# easyface485.net
KiCad netlist of a schematic drawn in EAGLE
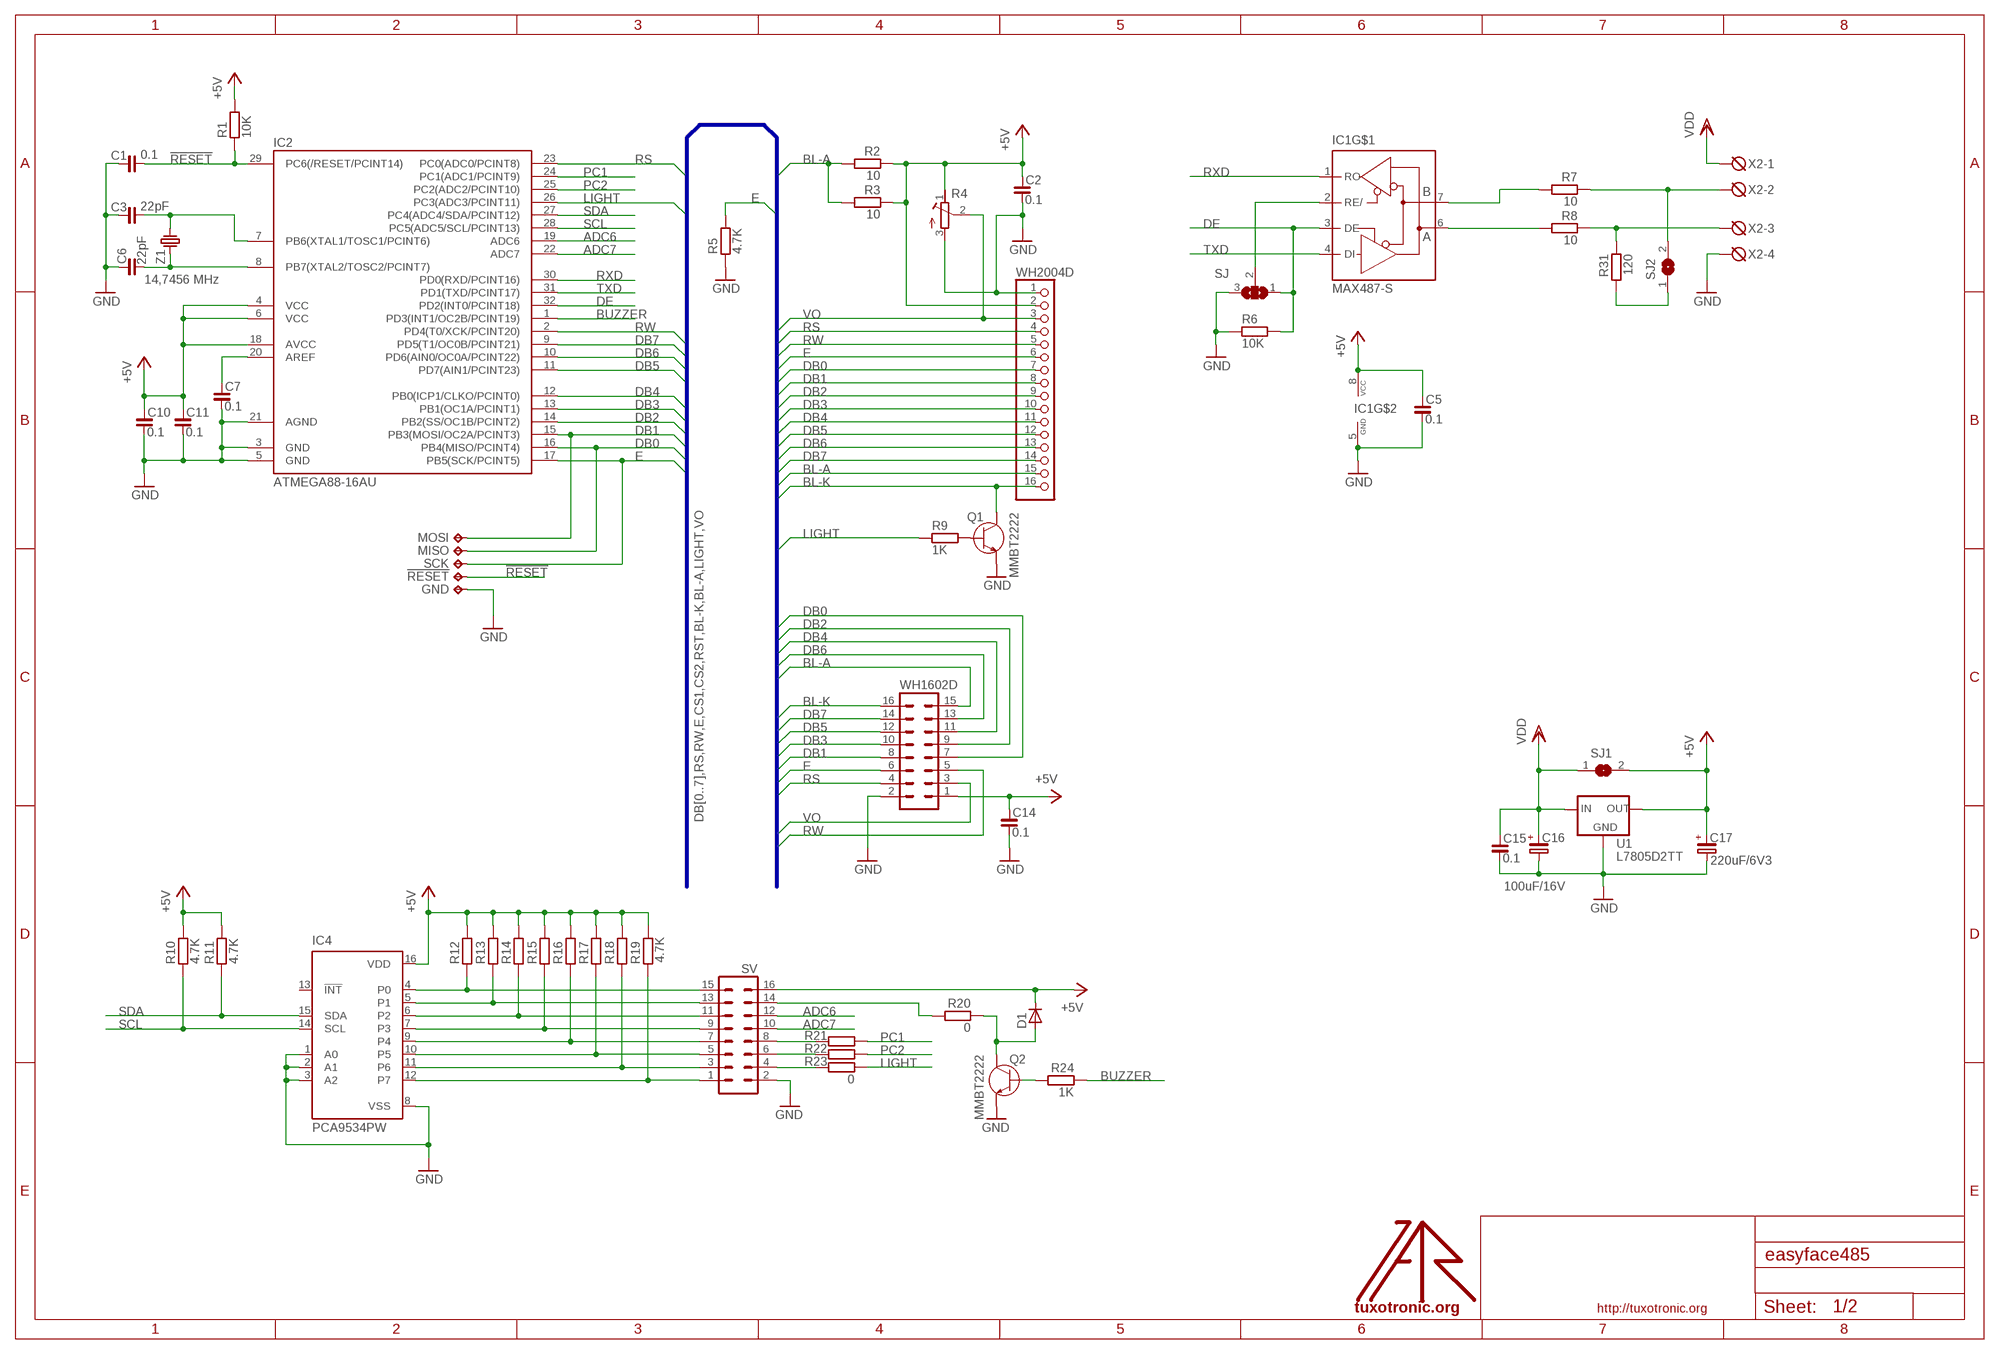
[diagram p0: schematic, sheet 1]
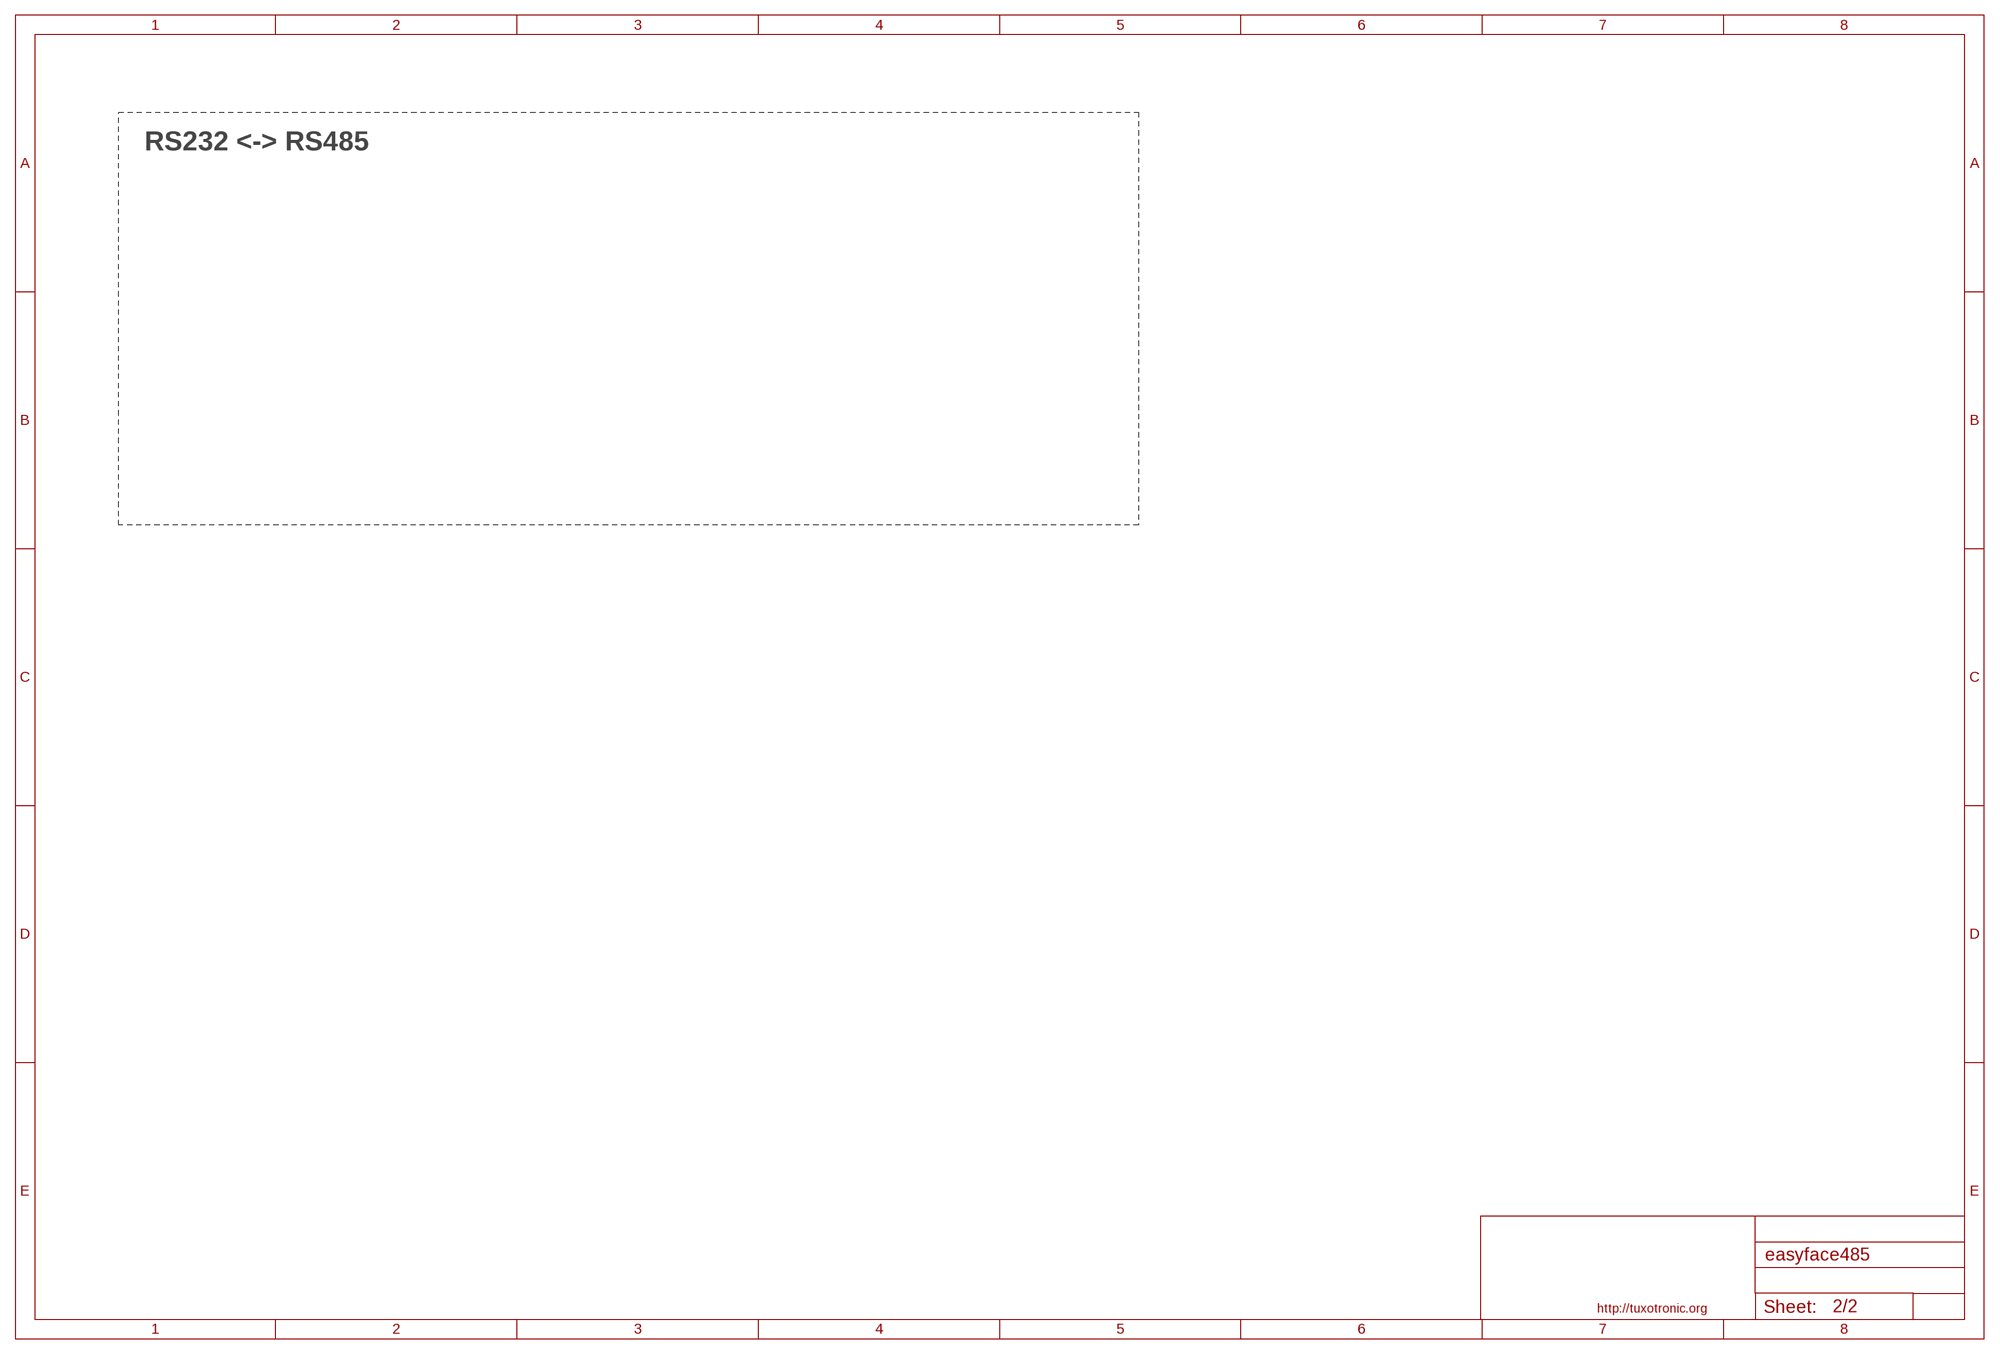
[diagram p1: schematic, sheet 2]

(export (version "E")
  (design (tool "Eeschema 10.0.6"))
  (components
    (comp (ref "!RESET")
      (value "TPB1,27")
      (footprint "eagle-import:B1,27")
      (libsource (lib "eagle-import") (part "TPB1,27"))
    )
    (comp (ref "C1")
      (value "0.1")
      (footprint "eagle-import:C0805")
      (libsource (lib "eagle-import") (part "C_0805"))
    )
    (comp (ref "C2")
      (value "0.1")
      (footprint "eagle-import:C0805")
      (libsource (lib "eagle-import") (part "C_0805"))
    )
    (comp (ref "C3")
      (value "22pF")
      (footprint "eagle-import:C0805")
      (libsource (lib "eagle-import") (part "C_0805"))
    )
    (comp (ref "C5")
      (value "0.1")
      (footprint "eagle-import:C0805")
      (libsource (lib "eagle-import") (part "C_0805"))
    )
    (comp (ref "C6")
      (value "22pF")
      (footprint "eagle-import:C0805")
      (libsource (lib "eagle-import") (part "C_0805"))
    )
    (comp (ref "C7")
      (value "0.1")
      (footprint "eagle-import:C0805")
      (libsource (lib "eagle-import") (part "C_0805"))
    )
    (comp (ref "C10")
      (value "0.1")
      (footprint "eagle-import:C0805")
      (libsource (lib "eagle-import") (part "C_0805"))
    )
    (comp (ref "C11")
      (value "0.1")
      (footprint "eagle-import:C0805")
      (libsource (lib "eagle-import") (part "C_0805"))
    )
    (comp (ref "C14")
      (value "0.1")
      (footprint "eagle-import:C0805")
      (libsource (lib "eagle-import") (part "C_0805"))
    )
    (comp (ref "C15")
      (value "0.1")
      (footprint "eagle-import:C0805")
      (libsource (lib "eagle-import") (part "C_0805"))
    )
    (comp (ref "C16")
      (value "100uF/16V")
      (footprint "eagle-import:SMC_D")
      (libsource (lib "eagle-import") (part "CP_SMCD"))
    )
    (comp (ref "C17")
      (value "220uF/6V3")
      (footprint "eagle-import:SMC_D")
      (libsource (lib "eagle-import") (part "CP_SMCD"))
    )
    (comp (ref "D1")
      (value "D-SOD-80")
      (footprint "eagle-import:SOD80")
      (libsource (lib "eagle-import") (part "D-SOD-80"))
    )
    (comp (ref "GND")
      (value "TPB1,27")
      (footprint "eagle-import:B1,27")
      (libsource (lib "eagle-import") (part "TPB1,27"))
    )
    (comp (ref "IC1")
      (value "MAX487-S")
      (footprint "eagle-import:SO08")
      (libsource (lib "eagle-import") (part "MAX487-S"))
    )
    (comp (ref "IC2")
      (value "ATMEGA88-16AU")
      (footprint "eagle-import:TQFP32-08")
      (libsource (lib "eagle-import") (part "MEGA48/88/168-AU"))
    )
    (comp (ref "IC4")
      (value "PCA9534PW")
      (footprint "eagle-import:SSOP16")
      (libsource (lib "eagle-import") (part "PCA9534PW"))
    )
    (comp (ref "MISO")
      (value "TPB1,27")
      (footprint "eagle-import:B1,27")
      (libsource (lib "eagle-import") (part "TPB1,27"))
    )
    (comp (ref "MOSI")
      (value "TPB1,27")
      (footprint "eagle-import:B1,27")
      (libsource (lib "eagle-import") (part "TPB1,27"))
    )
    (comp (ref "Q1")
      (value "MMBT2222")
      (footprint "eagle-import:SOT23")
      (libsource (lib "eagle-import") (part "BC847C"))
    )
    (comp (ref "Q2")
      (value "MMBT2222")
      (footprint "eagle-import:SOT23")
      (libsource (lib "eagle-import") (part "BC847C"))
    )
    (comp (ref "R1")
      (value "10K")
      (footprint "eagle-import:R0805")
      (libsource (lib "eagle-import") (part "R_0805"))
    )
    (comp (ref "R2")
      (value "10")
      (footprint "eagle-import:R0805")
      (libsource (lib "eagle-import") (part "R_0805"))
    )
    (comp (ref "R3")
      (value "10")
      (footprint "eagle-import:R0805")
      (libsource (lib "eagle-import") (part "R_0805"))
    )
    (comp (ref "R4")
      (value "RTRIM")
      (footprint "eagle-import:RTRIM-3362P")
      (libsource (lib "eagle-import") (part "RTRIM"))
    )
    (comp (ref "R5")
      (value "4.7K")
      (footprint "eagle-import:R0805")
      (libsource (lib "eagle-import") (part "R_0805"))
    )
    (comp (ref "R6")
      (value "10K")
      (footprint "eagle-import:R0805")
      (libsource (lib "eagle-import") (part "R_0805"))
    )
    (comp (ref "R7")
      (value "10")
      (footprint "eagle-import:R0805")
      (libsource (lib "eagle-import") (part "R_0805"))
    )
    (comp (ref "R8")
      (value "10")
      (footprint "eagle-import:R0805")
      (libsource (lib "eagle-import") (part "R_0805"))
    )
    (comp (ref "R9")
      (value "1K")
      (footprint "eagle-import:R0805")
      (libsource (lib "eagle-import") (part "R_0805"))
    )
    (comp (ref "R10")
      (value "4.7K")
      (footprint "eagle-import:R0805")
      (libsource (lib "eagle-import") (part "R_0805"))
    )
    (comp (ref "R11")
      (value "4.7K")
      (footprint "eagle-import:R0805")
      (libsource (lib "eagle-import") (part "R_0805"))
    )
    (comp (ref "R12")
      (value "4.7K")
      (footprint "eagle-import:R0805")
      (libsource (lib "eagle-import") (part "R_0805"))
    )
    (comp (ref "R13")
      (value "4.7K")
      (footprint "eagle-import:R0805")
      (libsource (lib "eagle-import") (part "R_0805"))
    )
    (comp (ref "R14")
      (value "4.7K")
      (footprint "eagle-import:R0805")
      (libsource (lib "eagle-import") (part "R_0805"))
    )
    (comp (ref "R15")
      (value "4.7K")
      (footprint "eagle-import:R0805")
      (libsource (lib "eagle-import") (part "R_0805"))
    )
    (comp (ref "R16")
      (value "4.7K")
      (footprint "eagle-import:R0805")
      (libsource (lib "eagle-import") (part "R_0805"))
    )
    (comp (ref "R17")
      (value "4.7K")
      (footprint "eagle-import:R0805")
      (libsource (lib "eagle-import") (part "R_0805"))
    )
    (comp (ref "R18")
      (value "4.7K")
      (footprint "eagle-import:R0805")
      (libsource (lib "eagle-import") (part "R_0805"))
    )
    (comp (ref "R19")
      (value "4.7K")
      (footprint "eagle-import:R0805")
      (libsource (lib "eagle-import") (part "R_0805"))
    )
    (comp (ref "R20")
      (value "0")
      (footprint "eagle-import:R0805")
      (libsource (lib "eagle-import") (part "R_0805"))
    )
    (comp (ref "R21")
      (value "0")
      (footprint "eagle-import:R0805")
      (libsource (lib "eagle-import") (part "R_0805"))
    )
    (comp (ref "R22")
      (value "0")
      (footprint "eagle-import:R0805")
      (libsource (lib "eagle-import") (part "R_0805"))
    )
    (comp (ref "R23")
      (value "0")
      (footprint "eagle-import:R0805")
      (libsource (lib "eagle-import") (part "R_0805"))
    )
    (comp (ref "R24")
      (value "1K")
      (footprint "eagle-import:R0805")
      (libsource (lib "eagle-import") (part "R_0805"))
    )
    (comp (ref "R31")
      (value "120")
      (footprint "eagle-import:R0805")
      (libsource (lib "eagle-import") (part "R_0805"))
    )
    (comp (ref "SCK")
      (value "TPB1,27")
      (footprint "eagle-import:B1,27")
      (libsource (lib "eagle-import") (part "TPB1,27"))
    )
    (comp (ref "SJ")
      (value "SJ2W")
      (footprint "eagle-import:SJ_2")
      (libsource (lib "eagle-import") (part "SJ2W"))
    )
    (comp (ref "SJ1") (value "SJ") (footprint "eagle-import:SJ") (libsource (lib "eagle-import") (part "SJ")))
    (comp (ref "SJ2") (value "SJ") (footprint "eagle-import:SJ") (libsource (lib "eagle-import") (part "SJ")))
    (comp (ref "SV")
      (value "ML16L")
      (footprint "eagle-import:ML16L")
      (libsource (lib "eagle-import") (part "ML16L"))
    )
    (comp (ref "U$")
      (value "LOGO")
      (footprint "eagle-import:TT_LOGO")
      (libsource (lib "eagle-import") (part "LOGO"))
    )
    (comp (ref "U1")
      (value "L7805D2TT")
      (footprint "eagle-import:D2PAK")
      (libsource (lib "eagle-import") (part "L78D2TT"))
    )
    (comp (ref "WH1602D")
      (value "MA08-2")
      (footprint "eagle-import:MA08-2")
      (libsource (lib "eagle-import") (part "MA08-2"))
    )
    (comp (ref "WH2004D")
      (value "PINHD-1X16_2.54-RND")
      (footprint "eagle-import:1X16RND")
      (libsource (lib "eagle-import") (part "PINHD-1X16_2.54-RND"))
    )
    (comp (ref "X2")
      (value "DG3XX-04-3.5")
      (footprint "eagle-import:DG350-3.5-04P")
      (libsource (lib "eagle-import") (part "DG3XX-04-3.5"))
    )
    (comp (ref "Z1")
      (value "14,7456 MHz")
      (footprint "eagle-import:HC49_S")
      (libsource (lib "eagle-import") (part "CRYSTAL-HC49S"))
    )
  )
  (nets
    (net (code "4") (name "+5V") (class "Default")
      (node (ref "C10") (pin "1") (pinfunction "1_1") (pintype "passive"))
      (node (ref "C11") (pin "1") (pinfunction "1_1") (pintype "passive"))
      (node (ref "C14") (pin "1") (pinfunction "1_1") (pintype "passive"))
      (node (ref "C17") (pin "+") (pinfunction "+_+") (pintype "passive"))
      (node (ref "C2") (pin "1") (pinfunction "1_1") (pintype "passive"))
      (node (ref "C5") (pin "1") (pinfunction "1_1") (pintype "passive"))
      (node (ref "D1") (pin "C") (pinfunction "C_C") (pintype "passive"))
      (node (ref "IC1") (pin "8") (pinfunction "VCC_8") (pintype "power_in"))
      (node (ref "IC2") (pin "18") (pinfunction "AVCC_18") (pintype "passive"))
      (node (ref "IC2") (pin "4") (pinfunction "VCC_4") (pintype "power_in"))
      (node (ref "IC2") (pin "6") (pinfunction "VCC_6") (pintype "power_in"))
      (node (ref "IC4") (pin "16") (pinfunction "VDD_16") (pintype "power_in"))
      (node (ref "R1") (pin "2") (pinfunction "2_2") (pintype "passive"))
      (node (ref "R10") (pin "2") (pinfunction "2_2") (pintype "passive"))
      (node (ref "R11") (pin "2") (pinfunction "2_2") (pintype "passive"))
      (node (ref "R12") (pin "2") (pinfunction "2_2") (pintype "passive"))
      (node (ref "R13") (pin "2") (pinfunction "2_2") (pintype "passive"))
      (node (ref "R14") (pin "2") (pinfunction "2_2") (pintype "passive"))
      (node (ref "R15") (pin "2") (pinfunction "2_2") (pintype "passive"))
      (node (ref "R16") (pin "2") (pinfunction "2_2") (pintype "passive"))
      (node (ref "R17") (pin "2") (pinfunction "2_2") (pintype "passive"))
      (node (ref "R18") (pin "2") (pinfunction "2_2") (pintype "passive"))
      (node (ref "R19") (pin "2") (pinfunction "2_2") (pintype "passive"))
      (node (ref "R2") (pin "1") (pinfunction "1_1") (pintype "passive"))
      (node (ref "R3") (pin "1") (pinfunction "1_1") (pintype "passive"))
      (node (ref "R4") (pin "1") (pinfunction "A_1") (pintype "passive"))
      (node (ref "SJ1") (pin "2") (pinfunction "2_2") (pintype "passive"))
      (node (ref "SV") (pin "16") (pinfunction "16_16") (pintype "passive"))
      (node (ref "U1") (pin "3") (pinfunction "OUT_3") (pintype "passive"))
      (node (ref "WH1602D") (pin "1") (pinfunction "1_1") (pintype "passive"))
      (node (ref "WH2004D") (pin "2") (pinfunction "2_2") (pintype "passive"))
    )
    (net (code "6") (name "ADC6") (class "Default")
      (node (ref "IC2") (pin "19") (pinfunction "ADC6_19") (pintype "passive"))
      (node (ref "SV") (pin "12") (pinfunction "12_12") (pintype "passive"))
    )
    (net (code "7") (name "ADC7") (class "Default")
      (node (ref "IC2") (pin "22") (pinfunction "ADC7_22") (pintype "passive"))
      (node (ref "SV") (pin "10") (pinfunction "10_10") (pintype "passive"))
    )
    (net (code "8") (name "BL-A") (class "Default")
      (node (ref "R2") (pin "2") (pinfunction "2_2") (pintype "passive"))
      (node (ref "R3") (pin "2") (pinfunction "2_2") (pintype "passive"))
      (node (ref "WH1602D") (pin "15") (pinfunction "15_15") (pintype "passive"))
      (node (ref "WH2004D") (pin "15") (pinfunction "15_15") (pintype "passive"))
    )
    (net (code "9") (name "BL-K") (class "Default")
      (node (ref "Q1") (pin "3") (pinfunction "C_3") (pintype "passive"))
      (node (ref "WH1602D") (pin "16") (pinfunction "16_16") (pintype "passive"))
      (node (ref "WH2004D") (pin "16") (pinfunction "16_16") (pintype "passive"))
    )
    (net (code "10") (name "BUZZER") (class "Default")
      (node (ref "IC2") (pin "1") (pinfunction "PD3(INT1/OC2B/PCINT19)_1") (pintype "bidirectional"))
      (node (ref "R24") (pin "1") (pinfunction "1_1") (pintype "passive"))
    )
    (net (code "11") (name "DB0") (class "Default")
      (node (ref "IC2") (pin "16") (pinfunction "PB4(MISO/PCINT4)_16") (pintype "bidirectional"))
      (node (ref "MISO") (pin "PP") (pinfunction "TP_PP") (pintype "input"))
      (node (ref "WH1602D") (pin "7") (pinfunction "7_7") (pintype "passive"))
      (node (ref "WH2004D") (pin "7") (pinfunction "7_7") (pintype "passive"))
    )
    (net (code "12") (name "DB1") (class "Default")
      (node (ref "IC2") (pin "15") (pinfunction "PB3(MOSI/OC2A/PCINT3)_15") (pintype "bidirectional"))
      (node (ref "MOSI") (pin "PP") (pinfunction "TP_PP") (pintype "input"))
      (node (ref "WH1602D") (pin "8") (pinfunction "8_8") (pintype "passive"))
      (node (ref "WH2004D") (pin "8") (pinfunction "8_8") (pintype "passive"))
    )
    (net (code "13") (name "DB2") (class "Default")
      (node (ref "IC2") (pin "14") (pinfunction "PB2(SS/OC1B/PCINT2)_14") (pintype "bidirectional"))
      (node (ref "WH1602D") (pin "9") (pinfunction "9_9") (pintype "passive"))
      (node (ref "WH2004D") (pin "9") (pinfunction "9_9") (pintype "passive"))
    )
    (net (code "14") (name "DB3") (class "Default")
      (node (ref "IC2") (pin "13") (pinfunction "PB1(OC1A/PCINT1)_13") (pintype "bidirectional"))
      (node (ref "WH1602D") (pin "10") (pinfunction "10_10") (pintype "passive"))
      (node (ref "WH2004D") (pin "10") (pinfunction "10_10") (pintype "passive"))
    )
    (net (code "15") (name "DB4") (class "Default")
      (node (ref "IC2") (pin "12") (pinfunction "PB0(ICP1/CLKO/PCINT0)_12") (pintype "bidirectional"))
      (node (ref "WH1602D") (pin "11") (pinfunction "11_11") (pintype "passive"))
      (node (ref "WH2004D") (pin "11") (pinfunction "11_11") (pintype "passive"))
    )
    (net (code "16") (name "DB5") (class "Default")
      (node (ref "IC2") (pin "11") (pinfunction "PD7(AIN1/PCINT23)_11") (pintype "bidirectional"))
      (node (ref "WH1602D") (pin "12") (pinfunction "12_12") (pintype "passive"))
      (node (ref "WH2004D") (pin "12") (pinfunction "12_12") (pintype "passive"))
    )
    (net (code "17") (name "DB6") (class "Default")
      (node (ref "IC2") (pin "10") (pinfunction "PD6(AIN0/OC0A/PCINT22)_10") (pintype "bidirectional"))
      (node (ref "WH1602D") (pin "13") (pinfunction "13_13") (pintype "passive"))
      (node (ref "WH2004D") (pin "13") (pinfunction "13_13") (pintype "passive"))
    )
    (net (code "18") (name "DB7") (class "Default")
      (node (ref "IC2") (pin "9") (pinfunction "PD5(T1/OC0B/PCINT21)_9") (pintype "bidirectional"))
      (node (ref "WH1602D") (pin "14") (pinfunction "14_14") (pintype "passive"))
      (node (ref "WH2004D") (pin "14") (pinfunction "14_14") (pintype "passive"))
    )
    (net (code "19") (name "DE") (class "Default")
      (node (ref "IC1") (pin "3") (pinfunction "DE_3") (pintype "input"))
      (node (ref "IC2") (pin "32") (pinfunction "PD2(INT0/PCINT18)_32") (pintype "bidirectional"))
      (node (ref "R6") (pin "2") (pinfunction "2_2") (pintype "passive"))
      (node (ref "SJ") (pin "1") (pinfunction "1_1") (pintype "passive"))
    )
    (net (code "20") (name "E") (class "Default")
      (node (ref "IC2") (pin "17") (pinfunction "PB5(SCK/PCINT5)_17") (pintype "bidirectional"))
      (node (ref "R5") (pin "2") (pinfunction "2_2") (pintype "passive"))
      (node (ref "SCK") (pin "PP") (pinfunction "TP_PP") (pintype "input"))
      (node (ref "WH1602D") (pin "6") (pinfunction "6_6") (pintype "passive"))
      (node (ref "WH2004D") (pin "6") (pinfunction "6_6") (pintype "passive"))
    )
    (net (code "21") (name "GND") (class "Default")
      (node (ref "C1") (pin "1") (pinfunction "1_1") (pintype "passive"))
      (node (ref "C10") (pin "2") (pinfunction "2_2") (pintype "passive"))
      (node (ref "C11") (pin "2") (pinfunction "2_2") (pintype "passive"))
      (node (ref "C14") (pin "2") (pinfunction "2_2") (pintype "passive"))
      (node (ref "C15") (pin "2") (pinfunction "2_2") (pintype "passive"))
      (node (ref "C16") (pin "-") (pinfunction "-_-") (pintype "passive"))
      (node (ref "C17") (pin "-") (pinfunction "-_-") (pintype "passive"))
      (node (ref "C2") (pin "2") (pinfunction "2_2") (pintype "passive"))
      (node (ref "C3") (pin "1") (pinfunction "1_1") (pintype "passive"))
      (node (ref "C5") (pin "2") (pinfunction "2_2") (pintype "passive"))
      (node (ref "C6") (pin "1") (pinfunction "1_1") (pintype "passive"))
      (node (ref "C7") (pin "2") (pinfunction "2_2") (pintype "passive"))
      (node (ref "GND") (pin "PP") (pinfunction "TP_PP") (pintype "input"))
      (node (ref "IC1") (pin "5") (pinfunction "GND_5") (pintype "power_in"))
      (node (ref "IC2") (pin "21") (pinfunction "AGND_21") (pintype "power_in"))
      (node (ref "IC2") (pin "3") (pinfunction "GND_3") (pintype "power_in"))
      (node (ref "IC2") (pin "5") (pinfunction "GND_5") (pintype "power_in"))
      (node (ref "IC4") (pin "1") (pinfunction "A0_1") (pintype "input"))
      (node (ref "IC4") (pin "2") (pinfunction "A1_2") (pintype "input"))
      (node (ref "IC4") (pin "3") (pinfunction "A2_3") (pintype "input"))
      (node (ref "IC4") (pin "8") (pinfunction "VSS_8") (pintype "power_in"))
      (node (ref "Q1") (pin "2") (pinfunction "E_2") (pintype "passive"))
      (node (ref "Q2") (pin "2") (pinfunction "E_2") (pintype "passive"))
      (node (ref "R4") (pin "3") (pinfunction "E_3") (pintype "passive"))
      (node (ref "R5") (pin "1") (pinfunction "1_1") (pintype "passive"))
      (node (ref "R6") (pin "1") (pinfunction "1_1") (pintype "passive"))
      (node (ref "SJ") (pin "3") (pinfunction "3_3") (pintype "passive"))
      (node (ref "SV") (pin "2") (pinfunction "2_2") (pintype "passive"))
      (node (ref "U1") (pin "2") (pinfunction "GND_2") (pintype "input"))
      (node (ref "WH1602D") (pin "2") (pinfunction "2_2") (pintype "passive"))
      (node (ref "WH2004D") (pin "1") (pinfunction "1_1") (pintype "passive"))
      (node (ref "X2") (pin "4") (pinfunction "KL_4") (pintype "passive"))
    )
    (net (code "22") (name "LIGHT") (class "Default")
      (node (ref "IC2") (pin "26") (pinfunction "PC3(ADC3/PCINT11)_26") (pintype "bidirectional"))
      (node (ref "R23") (pin "1") (pinfunction "1_1") (pintype "passive"))
      (node (ref "R9") (pin "1") (pinfunction "1_1") (pintype "passive"))
    )
    (net (code "23") (name "Net-(IC1A-A)") (class "Default")
      (node (ref "IC1") (pin "6") (pinfunction "A_6") (pintype "passive"))
      (node (ref "R8") (pin "2") (pinfunction "2_2") (pintype "passive"))
    )
    (net (code "24") (name "Net-(IC1A-B)") (class "Default")
      (node (ref "IC1") (pin "7") (pinfunction "B_7") (pintype "passive"))
      (node (ref "R7") (pin "2") (pinfunction "2_2") (pintype "passive"))
    )
    (net (code "25") (name "Net-(IC1A-RE{slash})") (class "Default")
      (node (ref "IC1") (pin "2") (pinfunction "RE/_2") (pintype "input"))
      (node (ref "SJ") (pin "2") (pinfunction "2_2") (pintype "passive"))
    )
    (net (code "26") (name "Net-(IC2-AREF)") (class "Default")
      (node (ref "C7") (pin "1") (pinfunction "1_1") (pintype "passive"))
      (node (ref "IC2") (pin "20") (pinfunction "AREF_20") (pintype "passive"))
    )
    (net (code "27") (name "Net-(IC2-PB6(XTAL1{slash}TOSC1{slash}PCINT6))") (class "Default")
      (node (ref "C3") (pin "2") (pinfunction "2_2") (pintype "passive"))
      (node (ref "IC2") (pin "7") (pinfunction "PB6(XTAL1/TOSC1/PCINT6)_7") (pintype "bidirectional"))
      (node (ref "Z1") (pin "2") (pinfunction "2_2") (pintype "passive"))
    )
    (net (code "28") (name "Net-(IC2-PB7(XTAL2{slash}TOSC2{slash}PCINT7))") (class "Default")
      (node (ref "C6") (pin "2") (pinfunction "2_2") (pintype "passive"))
      (node (ref "IC2") (pin "8") (pinfunction "PB7(XTAL2/TOSC2/PCINT7)_8") (pintype "bidirectional"))
      (node (ref "Z1") (pin "1") (pinfunction "1_1") (pintype "passive"))
    )
    (net (code "29") (name "Net-(IC4-P0)") (class "Default")
      (node (ref "IC4") (pin "4") (pinfunction "P0_4") (pintype "bidirectional"))
      (node (ref "R12") (pin "1") (pinfunction "1_1") (pintype "passive"))
      (node (ref "SV") (pin "15") (pinfunction "15_15") (pintype "passive"))
    )
    (net (code "30") (name "Net-(IC4-P1)") (class "Default")
      (node (ref "IC4") (pin "5") (pinfunction "P1_5") (pintype "bidirectional"))
      (node (ref "R13") (pin "1") (pinfunction "1_1") (pintype "passive"))
      (node (ref "SV") (pin "13") (pinfunction "13_13") (pintype "passive"))
    )
    (net (code "31") (name "Net-(IC4-P2)") (class "Default")
      (node (ref "IC4") (pin "6") (pinfunction "P2_6") (pintype "bidirectional"))
      (node (ref "R14") (pin "1") (pinfunction "1_1") (pintype "passive"))
      (node (ref "SV") (pin "11") (pinfunction "11_11") (pintype "passive"))
    )
    (net (code "32") (name "Net-(IC4-P3)") (class "Default")
      (node (ref "IC4") (pin "7") (pinfunction "P3_7") (pintype "bidirectional"))
      (node (ref "R15") (pin "1") (pinfunction "1_1") (pintype "passive"))
      (node (ref "SV") (pin "9") (pinfunction "9_9") (pintype "passive"))
    )
    (net (code "33") (name "Net-(IC4-P4)") (class "Default")
      (node (ref "IC4") (pin "9") (pinfunction "P4_9") (pintype "bidirectional"))
      (node (ref "R16") (pin "1") (pinfunction "1_1") (pintype "passive"))
      (node (ref "SV") (pin "7") (pinfunction "7_7") (pintype "passive"))
    )
    (net (code "34") (name "Net-(IC4-P5)") (class "Default")
      (node (ref "IC4") (pin "10") (pinfunction "P5_10") (pintype "bidirectional"))
      (node (ref "R17") (pin "1") (pinfunction "1_1") (pintype "passive"))
      (node (ref "SV") (pin "5") (pinfunction "5_5") (pintype "passive"))
    )
    (net (code "35") (name "Net-(IC4-P6)") (class "Default")
      (node (ref "IC4") (pin "11") (pinfunction "P6_11") (pintype "bidirectional"))
      (node (ref "R18") (pin "1") (pinfunction "1_1") (pintype "passive"))
      (node (ref "SV") (pin "3") (pinfunction "3_3") (pintype "passive"))
    )
    (net (code "36") (name "Net-(IC4-P7)") (class "Default")
      (node (ref "IC4") (pin "12") (pinfunction "P7_12") (pintype "bidirectional"))
      (node (ref "R19") (pin "1") (pinfunction "1_1") (pintype "passive"))
      (node (ref "SV") (pin "1") (pinfunction "1_1") (pintype "passive"))
    )
    (net (code "37") (name "Net-(Q1-B)") (class "Default")
      (node (ref "Q1") (pin "1") (pinfunction "B_1") (pintype "passive"))
      (node (ref "R9") (pin "2") (pinfunction "2_2") (pintype "passive"))
    )
    (net (code "38") (name "Net-(Q2-B)") (class "Default")
      (node (ref "Q2") (pin "1") (pinfunction "B_1") (pintype "passive"))
      (node (ref "R24") (pin "2") (pinfunction "2_2") (pintype "passive"))
    )
    (net (code "39") (name "Net-(Q2-C)") (class "Default")
      (node (ref "D1") (pin "A") (pinfunction "A_A") (pintype "passive"))
      (node (ref "Q2") (pin "3") (pinfunction "C_3") (pintype "passive"))
      (node (ref "R20") (pin "1") (pinfunction "1_1") (pintype "passive"))
    )
    (net (code "40") (name "Net-(R20-Pad2)") (class "Default")
      (node (ref "R20") (pin "2") (pinfunction "2_2") (pintype "passive"))
      (node (ref "SV") (pin "14") (pinfunction "14_14") (pintype "passive"))
    )
    (net (code "41") (name "Net-(R21-Pad2)") (class "Default")
      (node (ref "R21") (pin "2") (pinfunction "2_2") (pintype "passive"))
      (node (ref "SV") (pin "8") (pinfunction "8_8") (pintype "passive"))
    )
    (net (code "42") (name "Net-(R22-Pad2)") (class "Default")
      (node (ref "R22") (pin "2") (pinfunction "2_2") (pintype "passive"))
      (node (ref "SV") (pin "6") (pinfunction "6_6") (pintype "passive"))
    )
    (net (code "43") (name "Net-(R23-Pad2)") (class "Default")
      (node (ref "R23") (pin "2") (pinfunction "2_2") (pintype "passive"))
      (node (ref "SV") (pin "4") (pinfunction "4_4") (pintype "passive"))
    )
    (net (code "44") (name "Net-(R31-Pad2)") (class "Default")
      (node (ref "R31") (pin "2") (pinfunction "2_2") (pintype "passive"))
      (node (ref "SJ2") (pin "1") (pinfunction "1_1") (pintype "passive"))
    )
    (net (code "45") (name "Net-(X2B-KL)") (class "Default")
      (node (ref "R7") (pin "1") (pinfunction "1_1") (pintype "passive"))
      (node (ref "SJ2") (pin "2") (pinfunction "2_2") (pintype "passive"))
      (node (ref "X2") (pin "2") (pinfunction "KL_2") (pintype "passive"))
    )
    (net (code "46") (name "Net-(X2C-KL)") (class "Default")
      (node (ref "R31") (pin "1") (pinfunction "1_1") (pintype "passive"))
      (node (ref "R8") (pin "1") (pinfunction "1_1") (pintype "passive"))
      (node (ref "X2") (pin "3") (pinfunction "KL_3") (pintype "passive"))
    )
    (net (code "47") (name "PC1") (class "Default")
      (node (ref "IC2") (pin "24") (pinfunction "PC1(ADC1/PCINT9)_24") (pintype "bidirectional"))
      (node (ref "R21") (pin "1") (pinfunction "1_1") (pintype "passive"))
    )
    (net (code "48") (name "PC2") (class "Default")
      (node (ref "IC2") (pin "25") (pinfunction "PC2(ADC2/PCINT10)_25") (pintype "bidirectional"))
      (node (ref "R22") (pin "1") (pinfunction "1_1") (pintype "passive"))
    )
    (net (code "49") (name "RS") (class "Default")
      (node (ref "IC2") (pin "23") (pinfunction "PC0(ADC0/PCINT8)_23") (pintype "bidirectional"))
      (node (ref "WH1602D") (pin "4") (pinfunction "4_4") (pintype "passive"))
      (node (ref "WH2004D") (pin "4") (pinfunction "4_4") (pintype "passive"))
    )
    (net (code "50") (name "RW") (class "Default")
      (node (ref "IC2") (pin "2") (pinfunction "PD4(T0/XCK/PCINT20)_2") (pintype "bidirectional"))
      (node (ref "WH1602D") (pin "5") (pinfunction "5_5") (pintype "passive"))
      (node (ref "WH2004D") (pin "5") (pinfunction "5_5") (pintype "passive"))
    )
    (net (code "51") (name "RXD") (class "Default")
      (node (ref "IC1") (pin "1") (pinfunction "RO_1") (pintype "output"))
      (node (ref "IC2") (pin "30") (pinfunction "PD0(RXD/PCINT16)_30") (pintype "bidirectional"))
    )
    (net (code "52") (name "SCL") (class "Default")
      (node (ref "IC2") (pin "28") (pinfunction "PC5(ADC5/SCL/PCINT13)_28") (pintype "bidirectional"))
      (node (ref "IC4") (pin "14") (pinfunction "SCL_14") (pintype "input"))
      (node (ref "R10") (pin "1") (pinfunction "1_1") (pintype "passive"))
    )
    (net (code "53") (name "SDA") (class "Default")
      (node (ref "IC2") (pin "27") (pinfunction "PC4(ADC4/SDA/PCINT12)_27") (pintype "bidirectional"))
      (node (ref "IC4") (pin "15") (pinfunction "SDA_15") (pintype "bidirectional"))
      (node (ref "R11") (pin "1") (pinfunction "1_1") (pintype "passive"))
    )
    (net (code "54") (name "TXD") (class "Default")
      (node (ref "IC1") (pin "4") (pinfunction "DI_4") (pintype "input"))
      (node (ref "IC2") (pin "31") (pinfunction "PD1(TXD/PCINT17)_31") (pintype "bidirectional"))
    )
    (net (code "55") (name "VDD") (class "Default")
      (node (ref "C15") (pin "1") (pinfunction "1_1") (pintype "passive"))
      (node (ref "C16") (pin "+") (pinfunction "+_+") (pintype "passive"))
      (node (ref "SJ1") (pin "1") (pinfunction "1_1") (pintype "passive"))
      (node (ref "U1") (pin "1") (pinfunction "IN_1") (pintype "input"))
      (node (ref "X2") (pin "1") (pinfunction "KL_1") (pintype "passive"))
    )
    (net (code "56") (name "VO") (class "Default")
      (node (ref "R4") (pin "2") (pinfunction "S_2") (pintype "passive"))
      (node (ref "WH1602D") (pin "3") (pinfunction "3_3") (pintype "passive"))
      (node (ref "WH2004D") (pin "3") (pinfunction "3_3") (pintype "passive"))
    )
    (net (code "57") (name "unconnected-(IC4-~{INT}-Pad13)") (class "Default")
      (node (ref "IC4") (pin "13") (pinfunction "~{INT}_13") (pintype "output"))
    )
    (net (code "58") (name "~{RESET}") (class "Default")
      (node (ref "!RESET") (pin "PP") (pinfunction "TP_PP") (pintype "input"))
      (node (ref "C1") (pin "2") (pinfunction "2_2") (pintype "passive"))
      (node (ref "IC2") (pin "29") (pinfunction "PC6(/RESET/PCINT14)_29") (pintype "bidirectional"))
      (node (ref "R1") (pin "1") (pinfunction "1_1") (pintype "passive"))
    )
  )
)
